# 05_-_Motor_and_LEDs.net
KiCad netlist of a schematic drawn in Altium Designer
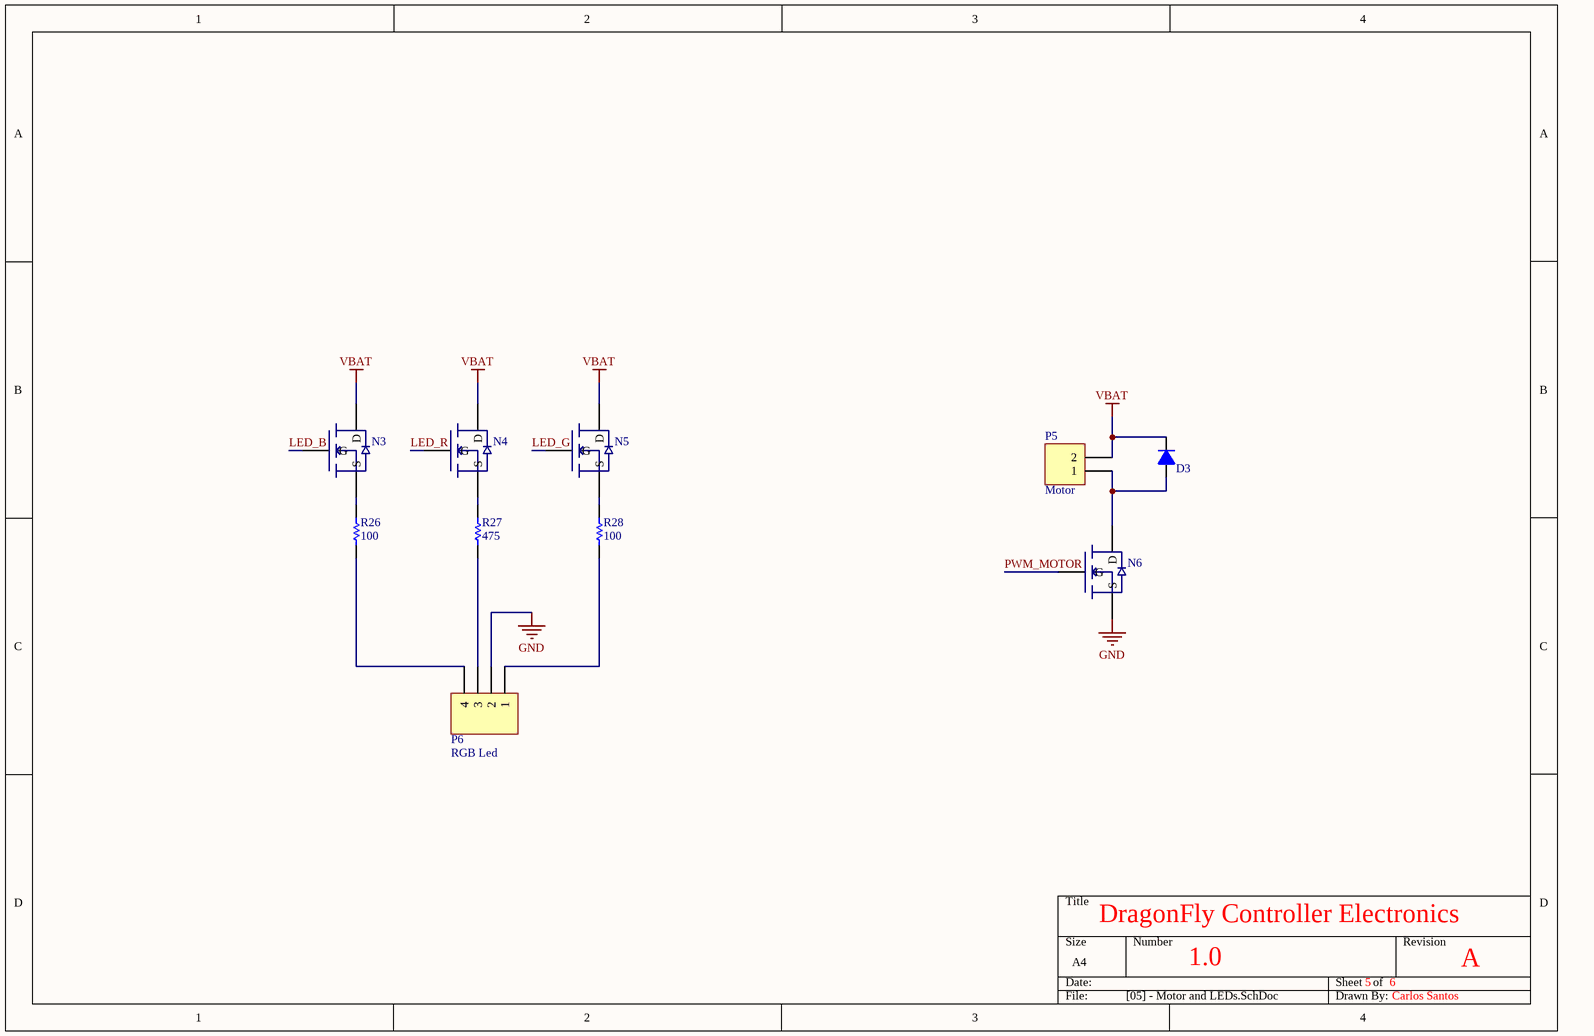
[diagram p0: [05] - Motor and LEDs.SchDoc]

(export (version "E")
  (design (tool "Eeschema 10.0.6"))
  (components
    (comp (ref "D3") (value "Diode") (footprint "0402 - Led") (libsource (lib "Mine") (part "Diode")))
    (comp (ref "N3") (value "N-MOSFET") (footprint "DFN1006-3") (libsource (lib "Mine") (part "N-MOSFET")))
    (comp (ref "N4") (value "N-MOSFET") (footprint "DFN1006-3") (libsource (lib "Mine") (part "N-MOSFET")))
    (comp (ref "N5") (value "N-MOSFET") (footprint "DFN1006-3") (libsource (lib "Mine") (part "N-MOSFET")))
    (comp (ref "N6") (value "N-MOSFET") (footprint "DFN1006-3") (libsource (lib "Mine") (part "N-MOSFET")))
    (comp (ref "P5")
      (value "Motor")
      (footprint "HDR1X2")
      (description "Header, 2-Pin")
      (fields (field (name "PUBLISHER") "Altium Limited"))
      (libsource (lib "Miscellaneous Connectors") (part "Header 2"))
    )
    (comp (ref "P6")
      (value "RGB Led")
      (footprint "HDR1X4")
      (description "Header, 4-Pin")
      (fields (field (name "DIGIKEY PART #") "1830-1015-ND") (field (name "PUBLISHER") "Altium Limited"))
      (libsource (lib "Miscellaneous Connectors") (part "Header 4"))
    )
    (comp (ref "R26")
      (value "100")
      (footprint "0402 - Resistor")
      (fields (field (name "Comment") "Resistor"))
      (libsource (lib "Mine") (part "Resistor"))
    )
    (comp (ref "R27")
      (value "475")
      (footprint "0402 - Resistor")
      (fields (field (name "Comment") "Resistor"))
      (libsource (lib "Mine") (part "Resistor"))
    )
    (comp (ref "R28")
      (value "100")
      (footprint "0402 - Resistor")
      (fields (field (name "Comment") "Resistor"))
      (libsource (lib "Mine") (part "Resistor"))
    )
  )
  (nets
    (net (code "1") (name "/LED_B") (class "Default")
      (node (ref "N3") (pin "2") (pinfunction "G_2") (pintype "passive"))
    )
    (net (code "2") (name "/LED_G") (class "Default")
      (node (ref "N5") (pin "2") (pinfunction "G_2") (pintype "passive"))
    )
    (net (code "3") (name "/LED_R") (class "Default")
      (node (ref "N4") (pin "2") (pinfunction "G_2") (pintype "passive"))
    )
    (net (code "4") (name "/PWM_MOTOR") (class "Default")
      (node (ref "N6") (pin "2") (pinfunction "G_2") (pintype "passive"))
    )
    (net (code "5") (name "GND") (class "Default")
      (node (ref "N6") (pin "1") (pinfunction "S_1") (pintype "passive"))
      (node (ref "P6") (pin "2") (pinfunction "2_2") (pintype "passive"))
    )
    (net (code "6") (name "Net-(D3-A)") (class "Default")
      (node (ref "D3") (pin "1") (pinfunction "A_1") (pintype "passive"))
      (node (ref "N6") (pin "3") (pinfunction "D_3") (pintype "passive"))
      (node (ref "P5") (pin "1") (pinfunction "1_1") (pintype "passive"))
    )
    (net (code "7") (name "Net-(N3-S)") (class "Default")
      (node (ref "N3") (pin "1") (pinfunction "S_1") (pintype "passive"))
      (node (ref "R26") (pin "2") (pinfunction "2_2") (pintype "passive"))
    )
    (net (code "8") (name "Net-(N4-S)") (class "Default")
      (node (ref "N4") (pin "1") (pinfunction "S_1") (pintype "passive"))
      (node (ref "R27") (pin "2") (pinfunction "2_2") (pintype "passive"))
    )
    (net (code "9") (name "Net-(N5-S)") (class "Default")
      (node (ref "N5") (pin "1") (pinfunction "S_1") (pintype "passive"))
      (node (ref "R28") (pin "2") (pinfunction "2_2") (pintype "passive"))
    )
    (net (code "10") (name "Net-(P6-Pad1)") (class "Default")
      (node (ref "P6") (pin "1") (pinfunction "1_1") (pintype "passive"))
      (node (ref "R28") (pin "1") (pinfunction "1_1") (pintype "passive"))
    )
    (net (code "11") (name "Net-(P6-Pad3)") (class "Default")
      (node (ref "P6") (pin "3") (pinfunction "3_3") (pintype "passive"))
      (node (ref "R27") (pin "1") (pinfunction "1_1") (pintype "passive"))
    )
    (net (code "12") (name "Net-(P6-Pad4)") (class "Default")
      (node (ref "P6") (pin "4") (pinfunction "4_4") (pintype "passive"))
      (node (ref "R26") (pin "1") (pinfunction "1_1") (pintype "passive"))
    )
    (net (code "13") (name "VBAT") (class "Default")
      (node (ref "D3") (pin "2") (pinfunction "K_2") (pintype "passive"))
      (node (ref "N3") (pin "3") (pinfunction "D_3") (pintype "passive"))
      (node (ref "N4") (pin "3") (pinfunction "D_3") (pintype "passive"))
      (node (ref "N5") (pin "3") (pinfunction "D_3") (pintype "passive"))
      (node (ref "P5") (pin "2") (pinfunction "2_2") (pintype "passive"))
    )
  )
)
